# ProtoPowerSupply.net
KiCad netlist of a schematic drawn in EAGLE
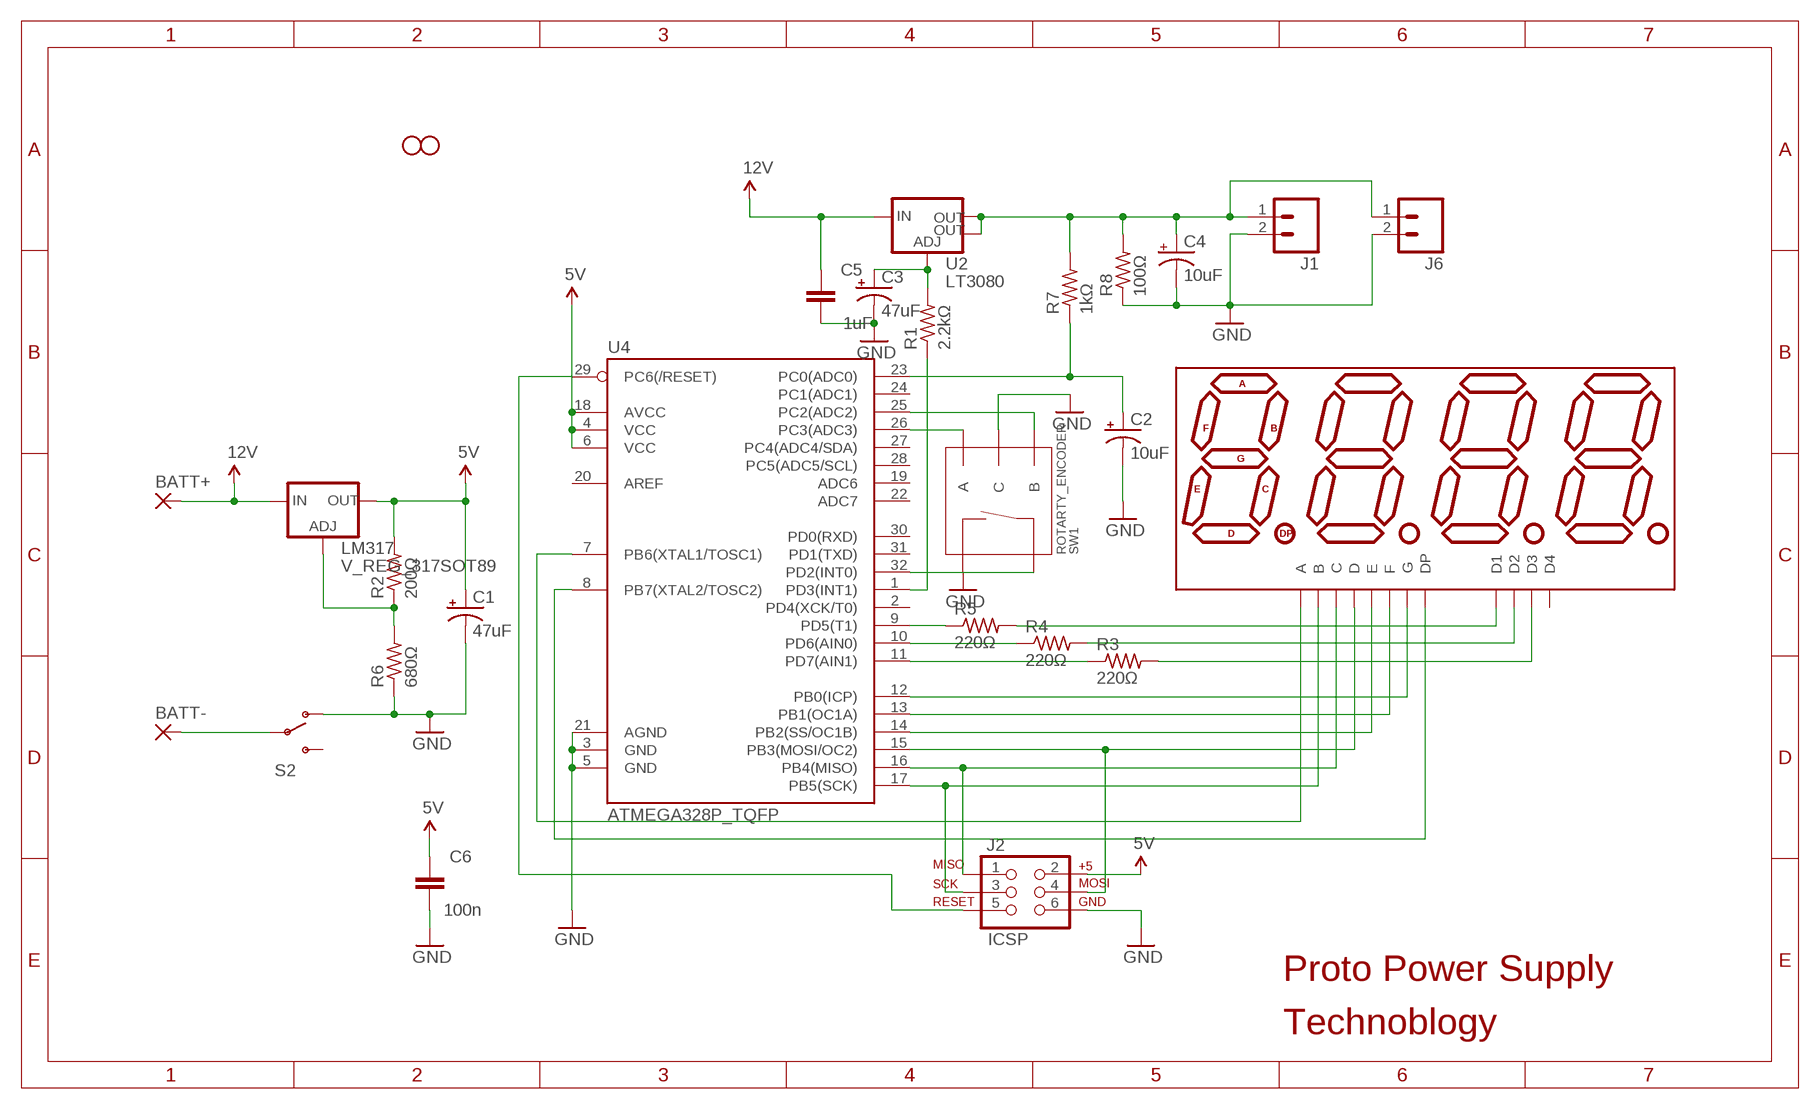
[diagram p0: schematic, sheet 1]

(export (version "E")
  (design (tool "Eeschema 10.0.6"))
  (components
    (comp (ref "BATT+")
      (value "1,6/0,9")
      (footprint "eagle-import:1,6_0,9")
      (libsource (lib "eagle-import") (part "1,6/0,9"))
    )
    (comp (ref "BATT-")
      (value "1,6/0,9")
      (footprint "eagle-import:1,6_0,9")
      (libsource (lib "eagle-import") (part "1,6/0,9"))
    )
    (comp (ref "C1")
      (value "47uF")
      (footprint "eagle-import:CPOL-RADIAL-10UF-25V")
      (libsource (lib "eagle-import") (part "CAP_POLPTH2"))
    )
    (comp (ref "C2")
      (value "10uF")
      (footprint "eagle-import:CPOL-RADIAL-10UF-25V")
      (libsource (lib "eagle-import") (part "CAP_POLPTH2"))
    )
    (comp (ref "C3")
      (value "47uF")
      (footprint "eagle-import:CPOL-RADIAL-10UF-25V")
      (libsource (lib "eagle-import") (part "CAP_POLPTH2"))
    )
    (comp (ref "C4")
      (value "10uF")
      (footprint "eagle-import:CPOL-RADIAL-10UF-25V")
      (libsource (lib "eagle-import") (part "CAP_POLPTH2"))
    )
    (comp (ref "C5")
      (value "1uF")
      (footprint "eagle-import:0603-CAP")
      (libsource (lib "eagle-import") (part "CAP0603-CAP"))
    )
    (comp (ref "C6")
      (value "100n")
      (footprint "eagle-import:0603-CAP")
      (libsource (lib "eagle-import") (part "CAP0603-CAP"))
    )
    (comp (ref "DISP1")
      (value "KYX-2381")
      (footprint "eagle-import:KYX-2381")
      (libsource (lib "eagle-import") (part "7-SEGMENT-4DIGIT-COUNTER-KYX-2381"))
    )
    (comp (ref "J1")
      (value "M021X02_NO_SILK")
      (footprint "eagle-import:1X02_NO_SILK")
      (libsource (lib "eagle-import") (part "M021X02_NO_SILK"))
    )
    (comp (ref "J2")
      (value "ICSP")
      (footprint "eagle-import:2X3")
      (libsource (lib "eagle-import") (part "AVR_SPI_PRG_6PTH"))
    )
    (comp (ref "J6")
      (value "M021X02_NO_SILK")
      (footprint "eagle-import:1X02_NO_SILK")
      (libsource (lib "eagle-import") (part "M021X02_NO_SILK"))
    )
    (comp (ref "JP4")
      (value "STAND-OFF")
      (footprint "eagle-import:STAND-OFF")
      (libsource (lib "eagle-import") (part "STAND-OFF"))
    )
    (comp (ref "JP5")
      (value "STAND-OFF")
      (footprint "eagle-import:STAND-OFF")
      (libsource (lib "eagle-import") (part "STAND-OFF"))
    )
    (comp (ref "LM317")
      (value "V_REG_317SOT89")
      (footprint "eagle-import:SOT89")
      (libsource (lib "eagle-import") (part "V_REG_317SOT89"))
    )
    (comp (ref "R1")
      (value "2.2kΩ")
      (footprint "eagle-import:R0805")
      (libsource (lib "eagle-import") (part "R-US_R0805"))
    )
    (comp (ref "R2")
      (value "200Ω")
      (footprint "eagle-import:R0805")
      (libsource (lib "eagle-import") (part "R-US_R0805"))
    )
    (comp (ref "R3")
      (value "220Ω")
      (footprint "eagle-import:R0805")
      (libsource (lib "eagle-import") (part "R-US_R0805"))
    )
    (comp (ref "R4")
      (value "220Ω")
      (footprint "eagle-import:R0805")
      (libsource (lib "eagle-import") (part "R-US_R0805"))
    )
    (comp (ref "R5")
      (value "220Ω")
      (footprint "eagle-import:R0805")
      (libsource (lib "eagle-import") (part "R-US_R0805"))
    )
    (comp (ref "R6")
      (value "680Ω")
      (footprint "eagle-import:R0805")
      (libsource (lib "eagle-import") (part "R-US_R0805"))
    )
    (comp (ref "R7")
      (value "1kΩ")
      (footprint "eagle-import:R0805")
      (libsource (lib "eagle-import") (part "R-US_R0805"))
    )
    (comp (ref "R8")
      (value "100Ω")
      (footprint "eagle-import:R0805")
      (libsource (lib "eagle-import") (part "R-US_R0805"))
    )
    (comp (ref "S2")
      (value "SWITCH-SPDTPTH")
      (footprint "eagle-import:SWITCH-SPDT")
      (libsource (lib "eagle-import") (part "SWITCH-SPDTPTH"))
    )
    (comp (ref "SW1")
      (value "ROTARTY_ENCODER")
      (footprint "eagle-import:ROTARY_ENC_PLAIN")
      (libsource (lib "eagle-import") (part "ROTARTY_ENCODER"))
    )
    (comp (ref "U2")
      (value "LT3080")
      (footprint "eagle-import:SOT223")
      (libsource (lib "eagle-import") (part "V_REG_LM1117SOT223"))
    )
    (comp (ref "U4")
      (value "ATMEGA328P_TQFP")
      (footprint "eagle-import:TQFP32-08")
      (libsource (lib "eagle-import") (part "ATMEGA328P_TQFP"))
    )
  )
  (nets
    (net (code "1") (name "5V") (class "Default")
      (node (ref "C1") (pin "1") (pinfunction "+_1") (pintype "passive"))
      (node (ref "C6") (pin "1") (pinfunction "1_1") (pintype "passive"))
      (node (ref "J2") (pin "2") (pinfunction "2_2") (pintype "passive"))
      (node (ref "LM317") (pin "2") (pinfunction "OUT_2") (pintype "output"))
      (node (ref "R2") (pin "2") (pinfunction "2_2") (pintype "passive"))
      (node (ref "U4") (pin "18") (pinfunction "AVCC_18") (pintype "bidirectional"))
      (node (ref "U4") (pin "4") (pinfunction "VCC_4") (pintype "bidirectional"))
      (node (ref "U4") (pin "6") (pinfunction "VCC_6") (pintype "bidirectional"))
    )
    (net (code "2") (name "12V") (class "Default")
      (node (ref "BATT+") (pin "1") (pinfunction "P_1") (pintype "passive"))
      (node (ref "C5") (pin "1") (pinfunction "1_1") (pintype "passive"))
      (node (ref "LM317") (pin "3") (pinfunction "IN_3") (pintype "input"))
      (node (ref "U2") (pin "3") (pinfunction "IN_3") (pintype "input"))
    )
    (net (code "3") (name "GND") (class "Default")
      (node (ref "C1") (pin "2") (pinfunction "-_2") (pintype "passive"))
      (node (ref "C2") (pin "2") (pinfunction "-_2") (pintype "passive"))
      (node (ref "C3") (pin "2") (pinfunction "-_2") (pintype "passive"))
      (node (ref "C4") (pin "2") (pinfunction "-_2") (pintype "passive"))
      (node (ref "C5") (pin "2") (pinfunction "2_2") (pintype "passive"))
      (node (ref "C6") (pin "2") (pinfunction "2_2") (pintype "passive"))
      (node (ref "J1") (pin "2") (pinfunction "2_2") (pintype "passive"))
      (node (ref "J2") (pin "6") (pinfunction "6_6") (pintype "passive"))
      (node (ref "J6") (pin "2") (pinfunction "2_2") (pintype "passive"))
      (node (ref "R6") (pin "1") (pinfunction "1_1") (pintype "passive"))
      (node (ref "R8") (pin "1") (pinfunction "1_1") (pintype "passive"))
      (node (ref "S2") (pin "1") (pinfunction "O_1") (pintype "passive"))
      (node (ref "SW1") (pin "C") (pinfunction "C_C") (pintype "bidirectional"))
      (node (ref "SW1") (pin "SW-") (pinfunction "SW-_SW-") (pintype "bidirectional"))
      (node (ref "U4") (pin "21") (pinfunction "AGND_21") (pintype "bidirectional"))
      (node (ref "U4") (pin "3") (pinfunction "GND_3") (pintype "bidirectional"))
      (node (ref "U4") (pin "5") (pinfunction "GND_5") (pintype "bidirectional"))
    )
    (net (code "4") (name "Net-(BATT--P)") (class "Default")
      (node (ref "BATT-") (pin "1") (pinfunction "P_1") (pintype "passive"))
      (node (ref "S2") (pin "2") (pinfunction "P_2") (pintype "passive"))
    )
    (net (code "5") (name "Net-(C2-+)") (class "Default")
      (node (ref "C2") (pin "1") (pinfunction "+_1") (pintype "passive"))
      (node (ref "R7") (pin "1") (pinfunction "1_1") (pintype "passive"))
      (node (ref "U4") (pin "23") (pinfunction "PC0(ADC0)_23") (pintype "bidirectional"))
    )
    (net (code "6") (name "Net-(C3-+)") (class "Default")
      (node (ref "C3") (pin "1") (pinfunction "+_1") (pintype "passive"))
      (node (ref "R1") (pin "2") (pinfunction "2_2") (pintype "passive"))
      (node (ref "U2") (pin "1") (pinfunction "ADJ_1") (pintype "input"))
    )
    (net (code "7") (name "Net-(C4-+)") (class "Default")
      (node (ref "C4") (pin "1") (pinfunction "+_1") (pintype "passive"))
      (node (ref "J1") (pin "1") (pinfunction "1_1") (pintype "passive"))
      (node (ref "J6") (pin "1") (pinfunction "1_1") (pintype "passive"))
      (node (ref "R7") (pin "2") (pinfunction "2_2") (pintype "passive"))
      (node (ref "R8") (pin "2") (pinfunction "2_2") (pintype "passive"))
      (node (ref "U2") (pin "2") (pinfunction "OUT_2") (pintype "output"))
      (node (ref "U2") (pin "4") (pinfunction "OUT_4") (pintype "output"))
    )
    (net (code "8") (name "Net-(DISP1-A)") (class "Default")
      (node (ref "DISP1") (pin "11") (pinfunction "A_11") (pintype "bidirectional"))
      (node (ref "U4") (pin "7") (pinfunction "PB6(XTAL1/TOSC1)_7") (pintype "bidirectional"))
    )
    (net (code "9") (name "Net-(DISP1-B)") (class "Default")
      (node (ref "DISP1") (pin "7") (pinfunction "B_7") (pintype "bidirectional"))
      (node (ref "J2") (pin "3") (pinfunction "3_3") (pintype "passive"))
      (node (ref "U4") (pin "17") (pinfunction "PB5(SCK)_17") (pintype "bidirectional"))
    )
    (net (code "10") (name "Net-(DISP1-C)") (class "Default")
      (node (ref "DISP1") (pin "4") (pinfunction "C_4") (pintype "bidirectional"))
      (node (ref "J2") (pin "1") (pinfunction "1_1") (pintype "passive"))
      (node (ref "U4") (pin "16") (pinfunction "PB4(MISO)_16") (pintype "bidirectional"))
    )
    (net (code "11") (name "Net-(DISP1-D)") (class "Default")
      (node (ref "DISP1") (pin "2") (pinfunction "D_2") (pintype "bidirectional"))
      (node (ref "J2") (pin "4") (pinfunction "4_4") (pintype "passive"))
      (node (ref "U4") (pin "15") (pinfunction "PB3(MOSI/OC2)_15") (pintype "bidirectional"))
    )
    (net (code "12") (name "Net-(DISP1-D1)") (class "Default")
      (node (ref "DISP1") (pin "12") (pinfunction "D1_12") (pintype "bidirectional"))
      (node (ref "R5") (pin "2") (pinfunction "2_2") (pintype "passive"))
    )
    (net (code "13") (name "Net-(DISP1-D2)") (class "Default")
      (node (ref "DISP1") (pin "9") (pinfunction "D2_9") (pintype "bidirectional"))
      (node (ref "R4") (pin "2") (pinfunction "2_2") (pintype "passive"))
    )
    (net (code "14") (name "Net-(DISP1-D3)") (class "Default")
      (node (ref "DISP1") (pin "8") (pinfunction "D3_8") (pintype "bidirectional"))
      (node (ref "R3") (pin "2") (pinfunction "2_2") (pintype "passive"))
    )
    (net (code "15") (name "Net-(DISP1-DP)") (class "Default")
      (node (ref "DISP1") (pin "3") (pinfunction "DP_3") (pintype "bidirectional"))
      (node (ref "U4") (pin "8") (pinfunction "PB7(XTAL2/TOSC2)_8") (pintype "bidirectional"))
    )
    (net (code "16") (name "Net-(DISP1-E)") (class "Default")
      (node (ref "DISP1") (pin "1") (pinfunction "E_1") (pintype "bidirectional"))
      (node (ref "U4") (pin "14") (pinfunction "PB2(SS/OC1B)_14") (pintype "bidirectional"))
    )
    (net (code "17") (name "Net-(DISP1-F)") (class "Default")
      (node (ref "DISP1") (pin "10") (pinfunction "F_10") (pintype "bidirectional"))
      (node (ref "U4") (pin "13") (pinfunction "PB1(OC1A)_13") (pintype "bidirectional"))
    )
    (net (code "18") (name "Net-(DISP1-G)") (class "Default")
      (node (ref "DISP1") (pin "5") (pinfunction "G_5") (pintype "bidirectional"))
      (node (ref "U4") (pin "12") (pinfunction "PB0(ICP)_12") (pintype "bidirectional"))
    )
    (net (code "19") (name "Net-(LM317-ADJ)") (class "Default")
      (node (ref "LM317") (pin "1") (pinfunction "ADJ_1") (pintype "input"))
      (node (ref "R2") (pin "1") (pinfunction "1_1") (pintype "passive"))
      (node (ref "R6") (pin "2") (pinfunction "2_2") (pintype "passive"))
    )
    (net (code "20") (name "Net-(U4-PC2(ADC2))") (class "Default")
      (node (ref "SW1") (pin "B") (pinfunction "B_B") (pintype "bidirectional"))
      (node (ref "U4") (pin "25") (pinfunction "PC2(ADC2)_25") (pintype "bidirectional"))
    )
    (net (code "21") (name "Net-(U4-PC3(ADC3))") (class "Default")
      (node (ref "SW1") (pin "A") (pinfunction "A_A") (pintype "bidirectional"))
      (node (ref "U4") (pin "26") (pinfunction "PC3(ADC3)_26") (pintype "bidirectional"))
    )
    (net (code "22") (name "Net-(U4-PC6({slash}RESET))") (class "Default")
      (node (ref "J2") (pin "5") (pinfunction "5_5") (pintype "passive"))
      (node (ref "U4") (pin "29") (pinfunction "PC6(/RESET)_29") (pintype "bidirectional"))
    )
    (net (code "23") (name "Net-(U4-PD2(INT0))") (class "Default")
      (node (ref "SW1") (pin "SW+") (pinfunction "SW+_SW+") (pintype "bidirectional"))
      (node (ref "U4") (pin "32") (pinfunction "PD2(INT0)_32") (pintype "bidirectional"))
    )
    (net (code "24") (name "Net-(U4-PD3(INT1))") (class "Default")
      (node (ref "R1") (pin "1") (pinfunction "1_1") (pintype "passive"))
      (node (ref "U4") (pin "1") (pinfunction "PD3(INT1)_1") (pintype "bidirectional"))
    )
    (net (code "25") (name "Net-(U4-PD5(T1))") (class "Default")
      (node (ref "R5") (pin "1") (pinfunction "1_1") (pintype "passive"))
      (node (ref "U4") (pin "9") (pinfunction "PD5(T1)_9") (pintype "bidirectional"))
    )
    (net (code "26") (name "Net-(U4-PD6(AIN0))") (class "Default")
      (node (ref "R4") (pin "1") (pinfunction "1_1") (pintype "passive"))
      (node (ref "U4") (pin "10") (pinfunction "PD6(AIN0)_10") (pintype "bidirectional"))
    )
    (net (code "27") (name "Net-(U4-PD7(AIN1))") (class "Default")
      (node (ref "R3") (pin "1") (pinfunction "1_1") (pintype "passive"))
      (node (ref "U4") (pin "11") (pinfunction "PD7(AIN1)_11") (pintype "bidirectional"))
    )
    (net (code "28") (name "unconnected-(DISP1-D4-Pad6)") (class "Default")
      (node (ref "DISP1") (pin "6") (pinfunction "D4_6") (pintype "bidirectional"))
    )
    (net (code "29") (name "unconnected-(S2-S-Pad3)") (class "Default")
      (node (ref "S2") (pin "3") (pinfunction "S_3") (pintype "passive"))
    )
    (net (code "30") (name "unconnected-(U4-ADC6-Pad19)") (class "Default")
      (node (ref "U4") (pin "19") (pinfunction "ADC6_19") (pintype "bidirectional"))
    )
    (net (code "31") (name "unconnected-(U4-ADC7-Pad22)") (class "Default")
      (node (ref "U4") (pin "22") (pinfunction "ADC7_22") (pintype "bidirectional"))
    )
    (net (code "32") (name "unconnected-(U4-AREF-Pad20)") (class "Default")
      (node (ref "U4") (pin "20") (pinfunction "AREF_20") (pintype "bidirectional"))
    )
    (net (code "33") (name "unconnected-(U4-PC1(ADC1)-Pad24)") (class "Default")
      (node (ref "U4") (pin "24") (pinfunction "PC1(ADC1)_24") (pintype "bidirectional"))
    )
    (net (code "34") (name "unconnected-(U4-PC4(ADC4{slash}SDA)-Pad27)") (class "Default")
      (node (ref "U4") (pin "27") (pinfunction "PC4(ADC4/SDA)_27") (pintype "bidirectional"))
    )
    (net (code "35") (name "unconnected-(U4-PC5(ADC5{slash}SCL)-Pad28)") (class "Default")
      (node (ref "U4") (pin "28") (pinfunction "PC5(ADC5/SCL)_28") (pintype "bidirectional"))
    )
    (net (code "36") (name "unconnected-(U4-PD0(RXD)-Pad30)") (class "Default")
      (node (ref "U4") (pin "30") (pinfunction "PD0(RXD)_30") (pintype "bidirectional"))
    )
    (net (code "37") (name "unconnected-(U4-PD1(TXD)-Pad31)") (class "Default")
      (node (ref "U4") (pin "31") (pinfunction "PD1(TXD)_31") (pintype "bidirectional"))
    )
    (net (code "38") (name "unconnected-(U4-PD4(XCK{slash}T0)-Pad2)") (class "Default")
      (node (ref "U4") (pin "2") (pinfunction "PD4(XCK/T0)_2") (pintype "bidirectional"))
    )
  )
)
